# amplifier.net
KiCad netlist of a schematic drawn in EAGLE
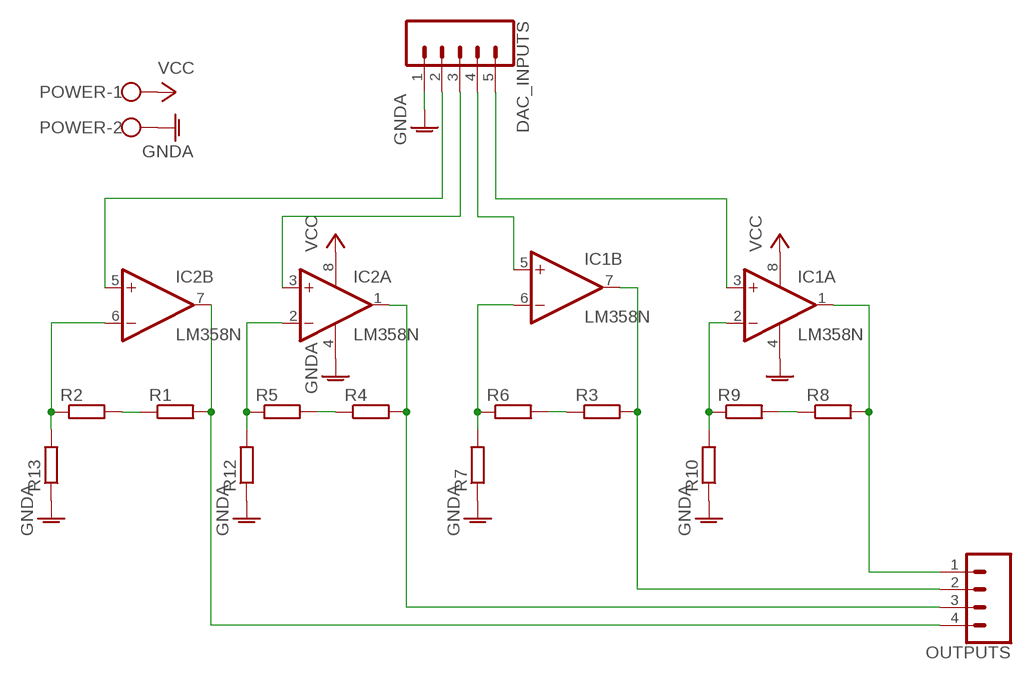
[diagram p0: schematic, sheet 1]

(export (version "E")
  (design (tool "Eeschema 10.0.6"))
  (components
    (comp (ref "DAC_INPUTS")
      (value "CONN_05")
      (footprint "eagle-import:1X05")
      (libsource (lib "eagle-import") (part "CONN_05"))
    )
    (comp (ref "IC1")
      (value "LM358N")
      (footprint "eagle-import:DIL08")
      (libsource (lib "eagle-import") (part "LM358N"))
    )
    (comp (ref "IC2")
      (value "LM358N")
      (footprint "eagle-import:DIL08")
      (libsource (lib "eagle-import") (part "LM358N"))
    )
    (comp (ref "OUTPUTS")
      (value "CONN_04")
      (footprint "eagle-import:1X04")
      (libsource (lib "eagle-import") (part "CONN_04"))
    )
    (comp (ref "POWER")
      (value "W237-102")
      (footprint "eagle-import:W237-102")
      (fields (field (name "MPN") "237-102"))
      (libsource (lib "eagle-import") (part "W237-102"))
    )
    (comp (ref "R1")
      (value "R-EU_0204/7")
      (footprint "eagle-import:0204_7")
      (libsource (lib "eagle-import") (part "R-EU_0204/7"))
    )
    (comp (ref "R2")
      (value "R-EU_0204/7")
      (footprint "eagle-import:0204_7")
      (libsource (lib "eagle-import") (part "R-EU_0204/7"))
    )
    (comp (ref "R3")
      (value "R-EU_0204/7")
      (footprint "eagle-import:0204_7")
      (libsource (lib "eagle-import") (part "R-EU_0204/7"))
    )
    (comp (ref "R4")
      (value "R-EU_0204/7")
      (footprint "eagle-import:0204_7")
      (libsource (lib "eagle-import") (part "R-EU_0204/7"))
    )
    (comp (ref "R5")
      (value "R-EU_0204/7")
      (footprint "eagle-import:0204_7")
      (libsource (lib "eagle-import") (part "R-EU_0204/7"))
    )
    (comp (ref "R6")
      (value "R-EU_0204/7")
      (footprint "eagle-import:0204_7")
      (libsource (lib "eagle-import") (part "R-EU_0204/7"))
    )
    (comp (ref "R7")
      (value "R-EU_0204/7")
      (footprint "eagle-import:0204_7")
      (libsource (lib "eagle-import") (part "R-EU_0204/7"))
    )
    (comp (ref "R8")
      (value "R-EU_0204/7")
      (footprint "eagle-import:0204_7")
      (libsource (lib "eagle-import") (part "R-EU_0204/7"))
    )
    (comp (ref "R9")
      (value "R-EU_0204/7")
      (footprint "eagle-import:0204_7")
      (libsource (lib "eagle-import") (part "R-EU_0204/7"))
    )
    (comp (ref "R10")
      (value "R-EU_0204/7")
      (footprint "eagle-import:0204_7")
      (libsource (lib "eagle-import") (part "R-EU_0204/7"))
    )
    (comp (ref "R12")
      (value "R-EU_0204/7")
      (footprint "eagle-import:0204_7")
      (libsource (lib "eagle-import") (part "R-EU_0204/7"))
    )
    (comp (ref "R13")
      (value "R-EU_0204/7")
      (footprint "eagle-import:0204_7")
      (libsource (lib "eagle-import") (part "R-EU_0204/7"))
    )
  )
  (nets
    (net (code "1") (name "GNDA") (class "Default")
      (node (ref "DAC_INPUTS") (pin "1") (pinfunction "1_1") (pintype "passive"))
      (node (ref "IC1") (pin "4") (pinfunction "V-_4") (pintype "power_in"))
      (node (ref "IC2") (pin "4") (pinfunction "V-_4") (pintype "power_in"))
      (node (ref "POWER") (pin "2") (pinfunction "KL_2") (pintype "passive"))
      (node (ref "R10") (pin "1") (pinfunction "1_1") (pintype "passive"))
      (node (ref "R12") (pin "1") (pinfunction "1_1") (pintype "passive"))
      (node (ref "R13") (pin "1") (pinfunction "1_1") (pintype "passive"))
      (node (ref "R7") (pin "1") (pinfunction "1_1") (pintype "passive"))
    )
    (net (code "2") (name "Net-(IC1A-+IN)") (class "Default")
      (node (ref "DAC_INPUTS") (pin "5") (pinfunction "5_5") (pintype "passive"))
      (node (ref "IC1") (pin "3") (pinfunction "+IN_3") (pintype "input"))
    )
    (net (code "3") (name "Net-(IC1A--IN)") (class "Default")
      (node (ref "IC1") (pin "2") (pinfunction "-IN_2") (pintype "input"))
      (node (ref "R10") (pin "2") (pinfunction "2_2") (pintype "passive"))
      (node (ref "R9") (pin "1") (pinfunction "1_1") (pintype "passive"))
    )
    (net (code "4") (name "Net-(IC1A-OUT)") (class "Default")
      (node (ref "IC1") (pin "1") (pinfunction "OUT_1") (pintype "output"))
      (node (ref "OUTPUTS") (pin "1") (pinfunction "1_1") (pintype "passive"))
      (node (ref "R8") (pin "2") (pinfunction "2_2") (pintype "passive"))
    )
    (net (code "5") (name "Net-(IC1B-+IN)") (class "Default")
      (node (ref "DAC_INPUTS") (pin "4") (pinfunction "4_4") (pintype "passive"))
      (node (ref "IC1") (pin "5") (pinfunction "+IN_5") (pintype "input"))
    )
    (net (code "6") (name "Net-(IC1B--IN)") (class "Default")
      (node (ref "IC1") (pin "6") (pinfunction "-IN_6") (pintype "input"))
      (node (ref "R6") (pin "1") (pinfunction "1_1") (pintype "passive"))
      (node (ref "R7") (pin "2") (pinfunction "2_2") (pintype "passive"))
    )
    (net (code "7") (name "Net-(IC1B-OUT)") (class "Default")
      (node (ref "IC1") (pin "7") (pinfunction "OUT_7") (pintype "output"))
      (node (ref "OUTPUTS") (pin "2") (pinfunction "2_2") (pintype "passive"))
      (node (ref "R3") (pin "2") (pinfunction "2_2") (pintype "passive"))
    )
    (net (code "8") (name "Net-(IC2A-+IN)") (class "Default")
      (node (ref "DAC_INPUTS") (pin "3") (pinfunction "3_3") (pintype "passive"))
      (node (ref "IC2") (pin "3") (pinfunction "+IN_3") (pintype "input"))
    )
    (net (code "9") (name "Net-(IC2A--IN)") (class "Default")
      (node (ref "IC2") (pin "2") (pinfunction "-IN_2") (pintype "input"))
      (node (ref "R12") (pin "2") (pinfunction "2_2") (pintype "passive"))
      (node (ref "R5") (pin "1") (pinfunction "1_1") (pintype "passive"))
    )
    (net (code "10") (name "Net-(IC2A-OUT)") (class "Default")
      (node (ref "IC2") (pin "1") (pinfunction "OUT_1") (pintype "output"))
      (node (ref "OUTPUTS") (pin "3") (pinfunction "3_3") (pintype "passive"))
      (node (ref "R4") (pin "2") (pinfunction "2_2") (pintype "passive"))
    )
    (net (code "11") (name "Net-(IC2B-+IN)") (class "Default")
      (node (ref "DAC_INPUTS") (pin "2") (pinfunction "2_2") (pintype "passive"))
      (node (ref "IC2") (pin "5") (pinfunction "+IN_5") (pintype "input"))
    )
    (net (code "12") (name "Net-(IC2B--IN)") (class "Default")
      (node (ref "IC2") (pin "6") (pinfunction "-IN_6") (pintype "input"))
      (node (ref "R13") (pin "2") (pinfunction "2_2") (pintype "passive"))
      (node (ref "R2") (pin "1") (pinfunction "1_1") (pintype "passive"))
    )
    (net (code "13") (name "Net-(IC2B-OUT)") (class "Default")
      (node (ref "IC2") (pin "7") (pinfunction "OUT_7") (pintype "output"))
      (node (ref "OUTPUTS") (pin "4") (pinfunction "4_4") (pintype "passive"))
      (node (ref "R1") (pin "2") (pinfunction "2_2") (pintype "passive"))
    )
    (net (code "14") (name "Net-(R1-Pad1)") (class "Default")
      (node (ref "R1") (pin "1") (pinfunction "1_1") (pintype "passive"))
      (node (ref "R2") (pin "2") (pinfunction "2_2") (pintype "passive"))
    )
    (net (code "15") (name "Net-(R3-Pad1)") (class "Default")
      (node (ref "R3") (pin "1") (pinfunction "1_1") (pintype "passive"))
      (node (ref "R6") (pin "2") (pinfunction "2_2") (pintype "passive"))
    )
    (net (code "16") (name "Net-(R4-Pad1)") (class "Default")
      (node (ref "R4") (pin "1") (pinfunction "1_1") (pintype "passive"))
      (node (ref "R5") (pin "2") (pinfunction "2_2") (pintype "passive"))
    )
    (net (code "17") (name "Net-(R8-Pad1)") (class "Default")
      (node (ref "R8") (pin "1") (pinfunction "1_1") (pintype "passive"))
      (node (ref "R9") (pin "2") (pinfunction "2_2") (pintype "passive"))
    )
    (net (code "18") (name "VCC") (class "Default")
      (node (ref "IC1") (pin "8") (pinfunction "V+_8") (pintype "power_in"))
      (node (ref "IC2") (pin "8") (pinfunction "V+_8") (pintype "power_in"))
      (node (ref "POWER") (pin "1") (pinfunction "KL_1") (pintype "passive"))
    )
  )
)
